# unonano.net
KiCad netlist of a schematic drawn in EAGLE
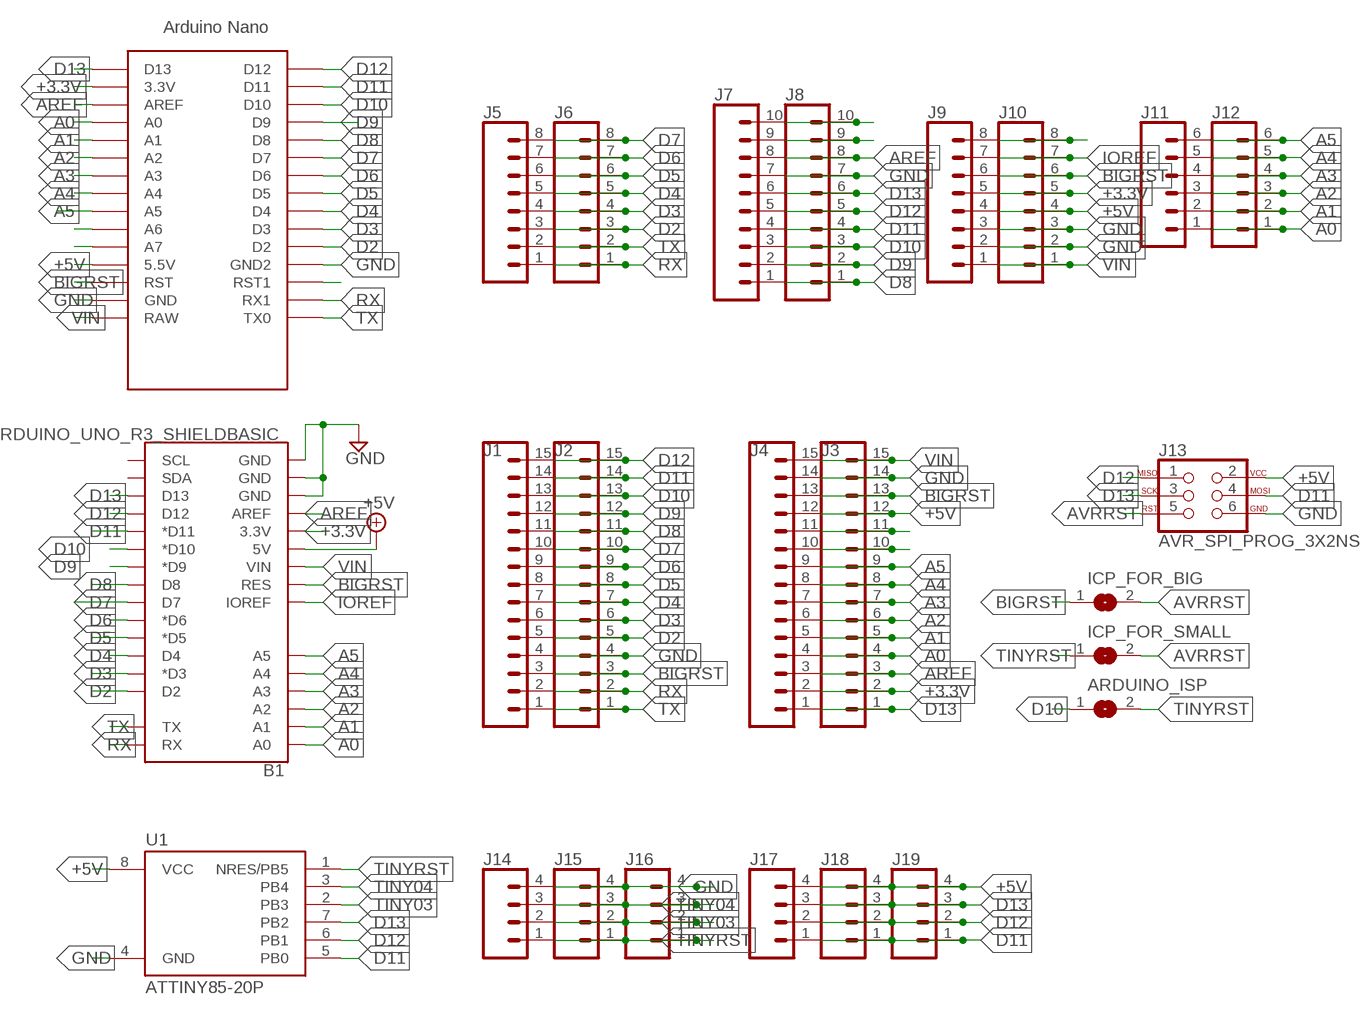
[diagram p0: schematic, sheet 1]

(export (version "E")
  (design (tool "Eeschema 10.0.6"))
  (components
    (comp (ref "ARDUINO_ISP")
      (value "SJ")
      (footprint "eagle-import:SJ")
      (libsource (lib "eagle-import") (part "SJ"))
    )
    (comp (ref "B1")
      (value "ARDUINO_UNO_R3_SHIELDBASIC")
      (footprint "eagle-import:UNO_R3_SHIELD")
      (libsource (lib "eagle-import") (part "ARDUINO_UNO_R3_SHIELDBASIC"))
    )
    (comp (ref "ICP_FOR_BIG")
      (value "SJ")
      (footprint "eagle-import:SJ")
      (libsource (lib "eagle-import") (part "SJ"))
    )
    (comp (ref "ICP_FOR_SMALL")
      (value "SJ")
      (footprint "eagle-import:SJ")
      (libsource (lib "eagle-import") (part "SJ"))
    )
    (comp (ref "J1")
      (value "CONN_15")
      (footprint "eagle-import:1X15")
      (libsource (lib "eagle-import") (part "CONN_15"))
    )
    (comp (ref "J2")
      (value "CONN_15")
      (footprint "eagle-import:1X15")
      (libsource (lib "eagle-import") (part "CONN_15"))
    )
    (comp (ref "J3")
      (value "CONN_15")
      (footprint "eagle-import:1X15")
      (libsource (lib "eagle-import") (part "CONN_15"))
    )
    (comp (ref "J4")
      (value "CONN_15")
      (footprint "eagle-import:1X15")
      (libsource (lib "eagle-import") (part "CONN_15"))
    )
    (comp (ref "J5")
      (value "CONN_08\"")
      (footprint "eagle-import:1X08")
      (libsource (lib "eagle-import") (part "CONN_08{dblquote}"))
    )
    (comp (ref "J6")
      (value "CONN_08\"")
      (footprint "eagle-import:1X08")
      (libsource (lib "eagle-import") (part "CONN_08{dblquote}"))
    )
    (comp (ref "J7")
      (value "CONN_10\"")
      (footprint "eagle-import:1X10")
      (libsource (lib "eagle-import") (part "CONN_10{dblquote}"))
    )
    (comp (ref "J8")
      (value "CONN_10\"")
      (footprint "eagle-import:1X10")
      (libsource (lib "eagle-import") (part "CONN_10{dblquote}"))
    )
    (comp (ref "J9")
      (value "CONN_08\"")
      (footprint "eagle-import:1X08")
      (libsource (lib "eagle-import") (part "CONN_08{dblquote}"))
    )
    (comp (ref "J10")
      (value "CONN_08\"")
      (footprint "eagle-import:1X08")
      (libsource (lib "eagle-import") (part "CONN_08{dblquote}"))
    )
    (comp (ref "J11")
      (value "CONN_06SILK_FEMALE_PTH")
      (footprint "eagle-import:1X06")
      (libsource (lib "eagle-import") (part "CONN_06SILK_FEMALE_PTH"))
    )
    (comp (ref "J12")
      (value "CONN_06SILK_FEMALE_PTH")
      (footprint "eagle-import:1X06")
      (libsource (lib "eagle-import") (part "CONN_06SILK_FEMALE_PTH"))
    )
    (comp (ref "J13")
      (value "AVR_SPI_PROG_3X2NS")
      (footprint "eagle-import:2X3-NS")
      (libsource (lib "eagle-import") (part "AVR_SPI_PROG_3X2NS"))
    )
    (comp (ref "J14")
      (value "CONN_04")
      (footprint "eagle-import:1X04")
      (libsource (lib "eagle-import") (part "CONN_04"))
    )
    (comp (ref "J15")
      (value "CONN_04")
      (footprint "eagle-import:1X04")
      (libsource (lib "eagle-import") (part "CONN_04"))
    )
    (comp (ref "J16")
      (value "CONN_04")
      (footprint "eagle-import:1X04")
      (libsource (lib "eagle-import") (part "CONN_04"))
    )
    (comp (ref "J17")
      (value "CONN_04")
      (footprint "eagle-import:1X04")
      (libsource (lib "eagle-import") (part "CONN_04"))
    )
    (comp (ref "J18")
      (value "CONN_04")
      (footprint "eagle-import:1X04")
      (libsource (lib "eagle-import") (part "CONN_04"))
    )
    (comp (ref "J19")
      (value "CONN_04")
      (footprint "eagle-import:1X04")
      (libsource (lib "eagle-import") (part "CONN_04"))
    )
    (comp (ref "U$1")
      (value "NANO")
      (footprint "eagle-import:NANO")
      (libsource (lib "eagle-import") (part "NANO"))
    )
    (comp (ref "U1")
      (value "ATTINY85-20P")
      (footprint "eagle-import:PDIP08_300MIL")
      (libsource (lib "eagle-import") (part "ATTINY85P-20"))
    )
  )
  (nets
    (net (code "1") (name "+3.3V") (class "Default")
      (node (ref "B1") (pin "3.3V") (pinfunction "3.3V_3.3V") (pintype "bidirectional"))
      (node (ref "J10") (pin "5") (pinfunction "5_5") (pintype "passive"))
      (node (ref "J3") (pin "2") (pinfunction "2_2") (pintype "passive"))
      (node (ref "J4") (pin "2") (pinfunction "2_2") (pintype "passive"))
      (node (ref "J9") (pin "5") (pinfunction "5_5") (pintype "passive"))
      (node (ref "U$1") (pin "3.3V") (pinfunction "3.3V_3.3V") (pintype "bidirectional"))
    )
    (net (code "2") (name "+5V") (class "Default")
      (node (ref "B1") (pin "5V") (pinfunction "5V_5V") (pintype "bidirectional"))
      (node (ref "J10") (pin "4") (pinfunction "4_4") (pintype "passive"))
      (node (ref "J13") (pin "2") (pinfunction "2_2") (pintype "passive"))
      (node (ref "J17") (pin "4") (pinfunction "4_4") (pintype "passive"))
      (node (ref "J18") (pin "4") (pinfunction "4_4") (pintype "passive"))
      (node (ref "J19") (pin "4") (pinfunction "4_4") (pintype "passive"))
      (node (ref "J3") (pin "12") (pinfunction "12_12") (pintype "passive"))
      (node (ref "J4") (pin "12") (pinfunction "12_12") (pintype "passive"))
      (node (ref "J9") (pin "4") (pinfunction "4_4") (pintype "passive"))
      (node (ref "U$1") (pin "5V") (pinfunction "5.5V_5V") (pintype "bidirectional"))
      (node (ref "U1") (pin "8") (pinfunction "VCC_8") (pintype "power_in"))
    )
    (net (code "3") (name "A0") (class "Default")
      (node (ref "B1") (pin "A0") (pinfunction "A0_A0") (pintype "bidirectional"))
      (node (ref "J11") (pin "1") (pinfunction "1_1") (pintype "passive"))
      (node (ref "J12") (pin "1") (pinfunction "1_1") (pintype "passive"))
      (node (ref "J3") (pin "4") (pinfunction "4_4") (pintype "passive"))
      (node (ref "J4") (pin "4") (pinfunction "4_4") (pintype "passive"))
      (node (ref "U$1") (pin "A0") (pinfunction "A0_A0") (pintype "bidirectional"))
    )
    (net (code "4") (name "A1") (class "Default")
      (node (ref "B1") (pin "A1") (pinfunction "A1_A1") (pintype "bidirectional"))
      (node (ref "J11") (pin "2") (pinfunction "2_2") (pintype "passive"))
      (node (ref "J12") (pin "2") (pinfunction "2_2") (pintype "passive"))
      (node (ref "J3") (pin "5") (pinfunction "5_5") (pintype "passive"))
      (node (ref "J4") (pin "5") (pinfunction "5_5") (pintype "passive"))
      (node (ref "U$1") (pin "A1") (pinfunction "A1_A1") (pintype "bidirectional"))
    )
    (net (code "5") (name "A2") (class "Default")
      (node (ref "B1") (pin "A2") (pinfunction "A2_A2") (pintype "bidirectional"))
      (node (ref "J11") (pin "3") (pinfunction "3_3") (pintype "passive"))
      (node (ref "J12") (pin "3") (pinfunction "3_3") (pintype "passive"))
      (node (ref "J3") (pin "6") (pinfunction "6_6") (pintype "passive"))
      (node (ref "J4") (pin "6") (pinfunction "6_6") (pintype "passive"))
      (node (ref "U$1") (pin "A2") (pinfunction "A2_A2") (pintype "bidirectional"))
    )
    (net (code "6") (name "A3") (class "Default")
      (node (ref "B1") (pin "A3") (pinfunction "A3_A3") (pintype "bidirectional"))
      (node (ref "J11") (pin "4") (pinfunction "4_4") (pintype "passive"))
      (node (ref "J12") (pin "4") (pinfunction "4_4") (pintype "passive"))
      (node (ref "J3") (pin "7") (pinfunction "7_7") (pintype "passive"))
      (node (ref "J4") (pin "7") (pinfunction "7_7") (pintype "passive"))
      (node (ref "U$1") (pin "A3") (pinfunction "A3_A3") (pintype "bidirectional"))
    )
    (net (code "7") (name "A4") (class "Default")
      (node (ref "B1") (pin "A4") (pinfunction "A4_A4") (pintype "bidirectional"))
      (node (ref "J11") (pin "5") (pinfunction "5_5") (pintype "passive"))
      (node (ref "J12") (pin "5") (pinfunction "5_5") (pintype "passive"))
      (node (ref "J3") (pin "8") (pinfunction "8_8") (pintype "passive"))
      (node (ref "J4") (pin "8") (pinfunction "8_8") (pintype "passive"))
      (node (ref "U$1") (pin "A4") (pinfunction "A4_A4") (pintype "bidirectional"))
    )
    (net (code "8") (name "A5") (class "Default")
      (node (ref "B1") (pin "A5") (pinfunction "A5_A5") (pintype "bidirectional"))
      (node (ref "J11") (pin "6") (pinfunction "6_6") (pintype "passive"))
      (node (ref "J12") (pin "6") (pinfunction "6_6") (pintype "passive"))
      (node (ref "J3") (pin "9") (pinfunction "9_9") (pintype "passive"))
      (node (ref "J4") (pin "9") (pinfunction "9_9") (pintype "passive"))
      (node (ref "U$1") (pin "A5") (pinfunction "A5_A5") (pintype "bidirectional"))
    )
    (net (code "9") (name "AREF") (class "Default")
      (node (ref "B1") (pin "AREF") (pinfunction "AREF_AREF") (pintype "bidirectional"))
      (node (ref "J3") (pin "3") (pinfunction "3_3") (pintype "passive"))
      (node (ref "J4") (pin "3") (pinfunction "3_3") (pintype "passive"))
      (node (ref "J7") (pin "8") (pinfunction "8_8") (pintype "passive"))
      (node (ref "J8") (pin "8") (pinfunction "8_8") (pintype "passive"))
      (node (ref "U$1") (pin "AREF") (pinfunction "AREF_AREF") (pintype "bidirectional"))
    )
    (net (code "10") (name "AVRRST") (class "Default")
      (node (ref "ICP_FOR_BIG") (pin "2") (pinfunction "2_2") (pintype "passive"))
      (node (ref "ICP_FOR_SMALL") (pin "2") (pinfunction "2_2") (pintype "passive"))
      (node (ref "J13") (pin "5") (pinfunction "5_5") (pintype "passive"))
    )
    (net (code "11") (name "BIGRST") (class "Default")
      (node (ref "B1") (pin "RES") (pinfunction "RES_RES") (pintype "bidirectional"))
      (node (ref "ICP_FOR_BIG") (pin "1") (pinfunction "1_1") (pintype "passive"))
      (node (ref "J1") (pin "3") (pinfunction "3_3") (pintype "passive"))
      (node (ref "J10") (pin "6") (pinfunction "6_6") (pintype "passive"))
      (node (ref "J2") (pin "3") (pinfunction "3_3") (pintype "passive"))
      (node (ref "J3") (pin "13") (pinfunction "13_13") (pintype "passive"))
      (node (ref "J4") (pin "13") (pinfunction "13_13") (pintype "passive"))
      (node (ref "J9") (pin "6") (pinfunction "6_6") (pintype "passive"))
      (node (ref "U$1") (pin "RST") (pinfunction "RST_RST") (pintype "bidirectional"))
    )
    (net (code "12") (name "D2") (class "Default")
      (node (ref "B1") (pin "D2") (pinfunction "D2_D2") (pintype "bidirectional"))
      (node (ref "J1") (pin "5") (pinfunction "5_5") (pintype "passive"))
      (node (ref "J2") (pin "5") (pinfunction "5_5") (pintype "passive"))
      (node (ref "J5") (pin "3") (pinfunction "3_3") (pintype "passive"))
      (node (ref "J6") (pin "3") (pinfunction "3_3") (pintype "passive"))
      (node (ref "U$1") (pin "D2") (pinfunction "D2_D2") (pintype "bidirectional"))
    )
    (net (code "13") (name "D3") (class "Default")
      (node (ref "B1") (pin "D3") (pinfunction "*D3_D3") (pintype "bidirectional"))
      (node (ref "J1") (pin "6") (pinfunction "6_6") (pintype "passive"))
      (node (ref "J2") (pin "6") (pinfunction "6_6") (pintype "passive"))
      (node (ref "J5") (pin "4") (pinfunction "4_4") (pintype "passive"))
      (node (ref "J6") (pin "4") (pinfunction "4_4") (pintype "passive"))
      (node (ref "U$1") (pin "D3") (pinfunction "D3_D3") (pintype "bidirectional"))
    )
    (net (code "14") (name "D4") (class "Default")
      (node (ref "B1") (pin "D4") (pinfunction "D4_D4") (pintype "bidirectional"))
      (node (ref "J1") (pin "7") (pinfunction "7_7") (pintype "passive"))
      (node (ref "J2") (pin "7") (pinfunction "7_7") (pintype "passive"))
      (node (ref "J5") (pin "5") (pinfunction "5_5") (pintype "passive"))
      (node (ref "J6") (pin "5") (pinfunction "5_5") (pintype "passive"))
      (node (ref "U$1") (pin "D4") (pinfunction "D4_D4") (pintype "bidirectional"))
    )
    (net (code "15") (name "D5") (class "Default")
      (node (ref "B1") (pin "D5") (pinfunction "*D5_D5") (pintype "bidirectional"))
      (node (ref "J1") (pin "8") (pinfunction "8_8") (pintype "passive"))
      (node (ref "J2") (pin "8") (pinfunction "8_8") (pintype "passive"))
      (node (ref "J5") (pin "6") (pinfunction "6_6") (pintype "passive"))
      (node (ref "J6") (pin "6") (pinfunction "6_6") (pintype "passive"))
      (node (ref "U$1") (pin "D5") (pinfunction "D5_D5") (pintype "bidirectional"))
    )
    (net (code "16") (name "D6") (class "Default")
      (node (ref "B1") (pin "D6") (pinfunction "*D6_D6") (pintype "bidirectional"))
      (node (ref "J1") (pin "9") (pinfunction "9_9") (pintype "passive"))
      (node (ref "J2") (pin "9") (pinfunction "9_9") (pintype "passive"))
      (node (ref "J5") (pin "7") (pinfunction "7_7") (pintype "passive"))
      (node (ref "J6") (pin "7") (pinfunction "7_7") (pintype "passive"))
      (node (ref "U$1") (pin "D6") (pinfunction "D6_D6") (pintype "bidirectional"))
    )
    (net (code "17") (name "D7") (class "Default")
      (node (ref "B1") (pin "D7") (pinfunction "D7_D7") (pintype "bidirectional"))
      (node (ref "J1") (pin "10") (pinfunction "10_10") (pintype "passive"))
      (node (ref "J2") (pin "10") (pinfunction "10_10") (pintype "passive"))
      (node (ref "J5") (pin "8") (pinfunction "8_8") (pintype "passive"))
      (node (ref "J6") (pin "8") (pinfunction "8_8") (pintype "passive"))
      (node (ref "U$1") (pin "D7") (pinfunction "D7_D7") (pintype "bidirectional"))
    )
    (net (code "18") (name "D8") (class "Default")
      (node (ref "B1") (pin "D8") (pinfunction "D8_D8") (pintype "bidirectional"))
      (node (ref "J1") (pin "11") (pinfunction "11_11") (pintype "passive"))
      (node (ref "J2") (pin "11") (pinfunction "11_11") (pintype "passive"))
      (node (ref "J7") (pin "1") (pinfunction "1_1") (pintype "passive"))
      (node (ref "J8") (pin "1") (pinfunction "1_1") (pintype "passive"))
      (node (ref "U$1") (pin "D8") (pinfunction "D8_D8") (pintype "bidirectional"))
    )
    (net (code "19") (name "D9") (class "Default")
      (node (ref "B1") (pin "D9") (pinfunction "*D9_D9") (pintype "bidirectional"))
      (node (ref "J1") (pin "12") (pinfunction "12_12") (pintype "passive"))
      (node (ref "J2") (pin "12") (pinfunction "12_12") (pintype "passive"))
      (node (ref "J7") (pin "2") (pinfunction "2_2") (pintype "passive"))
      (node (ref "J8") (pin "2") (pinfunction "2_2") (pintype "passive"))
      (node (ref "U$1") (pin "D9") (pinfunction "D9_D9") (pintype "bidirectional"))
    )
    (net (code "20") (name "D10") (class "Default")
      (node (ref "ARDUINO_ISP") (pin "1") (pinfunction "1_1") (pintype "passive"))
      (node (ref "B1") (pin "D10") (pinfunction "*D10_D10") (pintype "bidirectional"))
      (node (ref "J1") (pin "13") (pinfunction "13_13") (pintype "passive"))
      (node (ref "J2") (pin "13") (pinfunction "13_13") (pintype "passive"))
      (node (ref "J7") (pin "3") (pinfunction "3_3") (pintype "passive"))
      (node (ref "J8") (pin "3") (pinfunction "3_3") (pintype "passive"))
      (node (ref "U$1") (pin "D10") (pinfunction "D10_D10") (pintype "bidirectional"))
    )
    (net (code "21") (name "D11") (class "Default")
      (node (ref "B1") (pin "D11") (pinfunction "*D11_D11") (pintype "bidirectional"))
      (node (ref "J1") (pin "14") (pinfunction "14_14") (pintype "passive"))
      (node (ref "J13") (pin "4") (pinfunction "4_4") (pintype "passive"))
      (node (ref "J17") (pin "1") (pinfunction "1_1") (pintype "passive"))
      (node (ref "J18") (pin "1") (pinfunction "1_1") (pintype "passive"))
      (node (ref "J19") (pin "1") (pinfunction "1_1") (pintype "passive"))
      (node (ref "J2") (pin "14") (pinfunction "14_14") (pintype "passive"))
      (node (ref "J7") (pin "4") (pinfunction "4_4") (pintype "passive"))
      (node (ref "J8") (pin "4") (pinfunction "4_4") (pintype "passive"))
      (node (ref "U$1") (pin "D11") (pinfunction "D11_D11") (pintype "bidirectional"))
      (node (ref "U1") (pin "5") (pinfunction "PB0_5") (pintype "bidirectional"))
    )
    (net (code "22") (name "D12") (class "Default")
      (node (ref "B1") (pin "D12") (pinfunction "D12_D12") (pintype "bidirectional"))
      (node (ref "J1") (pin "15") (pinfunction "15_15") (pintype "passive"))
      (node (ref "J13") (pin "1") (pinfunction "1_1") (pintype "passive"))
      (node (ref "J17") (pin "2") (pinfunction "2_2") (pintype "passive"))
      (node (ref "J18") (pin "2") (pinfunction "2_2") (pintype "passive"))
      (node (ref "J19") (pin "2") (pinfunction "2_2") (pintype "passive"))
      (node (ref "J2") (pin "15") (pinfunction "15_15") (pintype "passive"))
      (node (ref "J7") (pin "5") (pinfunction "5_5") (pintype "passive"))
      (node (ref "J8") (pin "5") (pinfunction "5_5") (pintype "passive"))
      (node (ref "U$1") (pin "D12") (pinfunction "D12_D12") (pintype "bidirectional"))
      (node (ref "U1") (pin "6") (pinfunction "PB1_6") (pintype "bidirectional"))
    )
    (net (code "23") (name "D13") (class "Default")
      (node (ref "B1") (pin "D13") (pinfunction "D13_D13") (pintype "bidirectional"))
      (node (ref "J13") (pin "3") (pinfunction "3_3") (pintype "passive"))
      (node (ref "J17") (pin "3") (pinfunction "3_3") (pintype "passive"))
      (node (ref "J18") (pin "3") (pinfunction "3_3") (pintype "passive"))
      (node (ref "J19") (pin "3") (pinfunction "3_3") (pintype "passive"))
      (node (ref "J3") (pin "1") (pinfunction "1_1") (pintype "passive"))
      (node (ref "J4") (pin "1") (pinfunction "1_1") (pintype "passive"))
      (node (ref "J7") (pin "6") (pinfunction "6_6") (pintype "passive"))
      (node (ref "J8") (pin "6") (pinfunction "6_6") (pintype "passive"))
      (node (ref "U$1") (pin "D13") (pinfunction "D13_D13") (pintype "bidirectional"))
      (node (ref "U1") (pin "7") (pinfunction "PB2_7") (pintype "bidirectional"))
    )
    (net (code "24") (name "GND") (class "Default")
      (node (ref "B1") (pin "GND@0") (pinfunction "GND_GND@0") (pintype "bidirectional"))
      (node (ref "B1") (pin "GND@1") (pinfunction "GND_GND@1") (pintype "bidirectional"))
      (node (ref "B1") (pin "GND@2") (pinfunction "GND_GND@2") (pintype "bidirectional"))
      (node (ref "J1") (pin "4") (pinfunction "4_4") (pintype "passive"))
      (node (ref "J10") (pin "2") (pinfunction "2_2") (pintype "passive"))
      (node (ref "J10") (pin "3") (pinfunction "3_3") (pintype "passive"))
      (node (ref "J13") (pin "6") (pinfunction "6_6") (pintype "passive"))
      (node (ref "J14") (pin "4") (pinfunction "4_4") (pintype "passive"))
      (node (ref "J15") (pin "4") (pinfunction "4_4") (pintype "passive"))
      (node (ref "J16") (pin "4") (pinfunction "4_4") (pintype "passive"))
      (node (ref "J2") (pin "4") (pinfunction "4_4") (pintype "passive"))
      (node (ref "J3") (pin "14") (pinfunction "14_14") (pintype "passive"))
      (node (ref "J4") (pin "14") (pinfunction "14_14") (pintype "passive"))
      (node (ref "J7") (pin "7") (pinfunction "7_7") (pintype "passive"))
      (node (ref "J8") (pin "7") (pinfunction "7_7") (pintype "passive"))
      (node (ref "J9") (pin "2") (pinfunction "2_2") (pintype "passive"))
      (node (ref "J9") (pin "3") (pinfunction "3_3") (pintype "passive"))
      (node (ref "U$1") (pin "GND") (pinfunction "GND_GND") (pintype "bidirectional"))
      (node (ref "U$1") (pin "GND1") (pinfunction "GND2_GND1") (pintype "bidirectional"))
      (node (ref "U1") (pin "4") (pinfunction "GND_4") (pintype "power_in"))
    )
    (net (code "25") (name "IOREF") (class "Default")
      (node (ref "B1") (pin "IOREF") (pinfunction "IOREF_IOREF") (pintype "bidirectional"))
      (node (ref "J10") (pin "7") (pinfunction "7_7") (pintype "passive"))
      (node (ref "J9") (pin "7") (pinfunction "7_7") (pintype "passive"))
    )
    (net (code "26") (name "Net-(J3-Pad10)") (class "Default")
      (node (ref "J3") (pin "10") (pinfunction "10_10") (pintype "passive"))
      (node (ref "J4") (pin "10") (pinfunction "10_10") (pintype "passive"))
    )
    (net (code "27") (name "Net-(J3-Pad11)") (class "Default")
      (node (ref "J3") (pin "11") (pinfunction "11_11") (pintype "passive"))
      (node (ref "J4") (pin "11") (pinfunction "11_11") (pintype "passive"))
    )
    (net (code "28") (name "Net-(J7-Pad9)") (class "Default")
      (node (ref "J7") (pin "9") (pinfunction "9_9") (pintype "passive"))
      (node (ref "J8") (pin "9") (pinfunction "9_9") (pintype "passive"))
    )
    (net (code "29") (name "Net-(J7-Pad10)") (class "Default")
      (node (ref "J7") (pin "10") (pinfunction "10_10") (pintype "passive"))
      (node (ref "J8") (pin "10") (pinfunction "10_10") (pintype "passive"))
    )
    (net (code "30") (name "Net-(J10-Pad8)") (class "Default")
      (node (ref "J10") (pin "8") (pinfunction "8_8") (pintype "passive"))
      (node (ref "J9") (pin "8") (pinfunction "8_8") (pintype "passive"))
    )
    (net (code "31") (name "RX") (class "Default")
      (node (ref "B1") (pin "RX") (pinfunction "RX_RX") (pintype "bidirectional"))
      (node (ref "J1") (pin "2") (pinfunction "2_2") (pintype "passive"))
      (node (ref "J2") (pin "2") (pinfunction "2_2") (pintype "passive"))
      (node (ref "J5") (pin "1") (pinfunction "1_1") (pintype "passive"))
      (node (ref "J6") (pin "1") (pinfunction "1_1") (pintype "passive"))
      (node (ref "U$1") (pin "RX1") (pinfunction "RX1_RX1") (pintype "bidirectional"))
    )
    (net (code "32") (name "TINY03") (class "Default")
      (node (ref "J14") (pin "2") (pinfunction "2_2") (pintype "passive"))
      (node (ref "J15") (pin "2") (pinfunction "2_2") (pintype "passive"))
      (node (ref "J16") (pin "2") (pinfunction "2_2") (pintype "passive"))
      (node (ref "U1") (pin "2") (pinfunction "PB3_2") (pintype "bidirectional"))
    )
    (net (code "33") (name "TINY04") (class "Default")
      (node (ref "J14") (pin "3") (pinfunction "3_3") (pintype "passive"))
      (node (ref "J15") (pin "3") (pinfunction "3_3") (pintype "passive"))
      (node (ref "J16") (pin "3") (pinfunction "3_3") (pintype "passive"))
      (node (ref "U1") (pin "3") (pinfunction "PB4_3") (pintype "bidirectional"))
    )
    (net (code "34") (name "TINYRST") (class "Default")
      (node (ref "ARDUINO_ISP") (pin "2") (pinfunction "2_2") (pintype "passive"))
      (node (ref "ICP_FOR_SMALL") (pin "1") (pinfunction "1_1") (pintype "passive"))
      (node (ref "J14") (pin "1") (pinfunction "1_1") (pintype "passive"))
      (node (ref "J15") (pin "1") (pinfunction "1_1") (pintype "passive"))
      (node (ref "J16") (pin "1") (pinfunction "1_1") (pintype "passive"))
      (node (ref "U1") (pin "1") (pinfunction "NRES/PB5_1") (pintype "bidirectional"))
    )
    (net (code "35") (name "TX") (class "Default")
      (node (ref "B1") (pin "TX") (pinfunction "TX_TX") (pintype "bidirectional"))
      (node (ref "J1") (pin "1") (pinfunction "1_1") (pintype "passive"))
      (node (ref "J2") (pin "1") (pinfunction "1_1") (pintype "passive"))
      (node (ref "J5") (pin "2") (pinfunction "2_2") (pintype "passive"))
      (node (ref "J6") (pin "2") (pinfunction "2_2") (pintype "passive"))
      (node (ref "U$1") (pin "TX0") (pinfunction "TX0_TX0") (pintype "bidirectional"))
    )
    (net (code "36") (name "VIN") (class "Default")
      (node (ref "B1") (pin "VIN") (pinfunction "VIN_VIN") (pintype "bidirectional"))
      (node (ref "J10") (pin "1") (pinfunction "1_1") (pintype "passive"))
      (node (ref "J3") (pin "15") (pinfunction "15_15") (pintype "passive"))
      (node (ref "J4") (pin "15") (pinfunction "15_15") (pintype "passive"))
      (node (ref "J9") (pin "1") (pinfunction "1_1") (pintype "passive"))
      (node (ref "U$1") (pin "RAW") (pinfunction "RAW_RAW") (pintype "bidirectional"))
    )
    (net (code "37") (name "unconnected-(B1-PadSCL)") (class "Default")
      (node (ref "B1") (pin "SCL") (pinfunction "SCL_SCL") (pintype "bidirectional"))
    )
    (net (code "38") (name "unconnected-(B1-PadSDA)") (class "Default")
      (node (ref "B1") (pin "SDA") (pinfunction "SDA_SDA") (pintype "bidirectional"))
    )
    (net (code "39") (name "unconnected-(U$1-PadA6)") (class "Default")
      (node (ref "U$1") (pin "A6") (pinfunction "A6_A6") (pintype "bidirectional"))
    )
    (net (code "40") (name "unconnected-(U$1-PadA7)") (class "Default")
      (node (ref "U$1") (pin "A7") (pinfunction "A7_A7") (pintype "bidirectional"))
    )
    (net (code "41") (name "unconnected-(U$1-PadICSP1)") (class "Default")
      (node (ref "U$1") (pin "ICSP1") (pinfunction "ICSP1_ICSP1") (pintype "bidirectional"))
    )
    (net (code "42") (name "unconnected-(U$1-PadICSP2)") (class "Default")
      (node (ref "U$1") (pin "ICSP2") (pinfunction "ICSP2_ICSP2") (pintype "bidirectional"))
    )
    (net (code "43") (name "unconnected-(U$1-PadICSP3)") (class "Default")
      (node (ref "U$1") (pin "ICSP3") (pinfunction "ICSP3_ICSP3") (pintype "bidirectional"))
    )
    (net (code "44") (name "unconnected-(U$1-PadICSP4)") (class "Default")
      (node (ref "U$1") (pin "ICSP4") (pinfunction "ICSP4_ICSP4") (pintype "bidirectional"))
    )
    (net (code "45") (name "unconnected-(U$1-PadICSP5)") (class "Default")
      (node (ref "U$1") (pin "ICSP5") (pinfunction "ICSP5_ICSP5") (pintype "bidirectional"))
    )
    (net (code "46") (name "unconnected-(U$1-PadICSP6)") (class "Default")
      (node (ref "U$1") (pin "ICSP6") (pinfunction "ICSP6_ICSP6") (pintype "bidirectional"))
    )
    (net (code "47") (name "unconnected-(U$1-PadRST1)") (class "Default")
      (node (ref "U$1") (pin "RST1") (pinfunction "RST1_RST1") (pintype "bidirectional"))
    )
  )
)
